# UKHASnet-avr-sensor.net
KiCad netlist of a schematic drawn in EAGLE
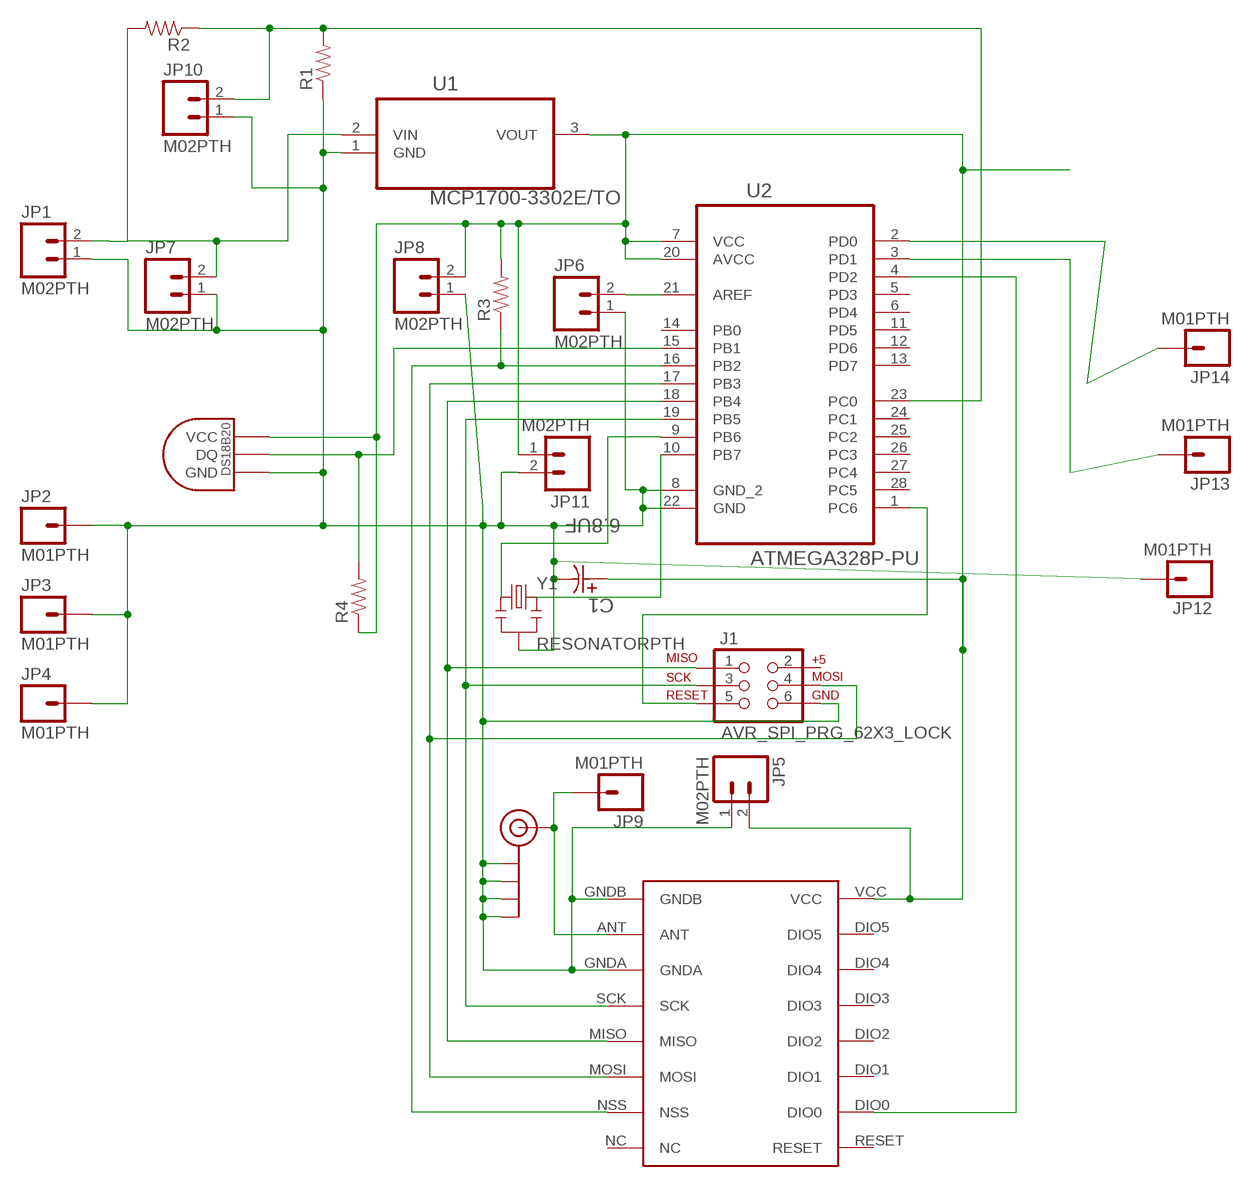
[diagram p0: schematic, sheet 1]

(export (version "E")
  (design (tool "Eeschema 10.0.6"))
  (components
    (comp (ref "C1")
      (value "6.8UF")
      (footprint "eagle-import:CAPPR150-400X1200")
      (fields (field (name "MPN") "EEUFC1J6R8") (field (name "TOLERANCE") "±20 %"))
      (libsource (lib "eagle-import") (part "EEU-P1.5FC1J6R8"))
    )
    (comp (ref "J$1")
      (value "SMA_EDGE")
      (footprint "eagle-import:SMA-EDGE")
      (libsource (lib "eagle-import") (part "SMA_EDGE"))
    )
    (comp (ref "J1")
      (value "AVR_SPI_PRG_62X3_LOCK")
      (footprint "eagle-import:2X3_LOCK")
      (libsource (lib "eagle-import") (part "AVR_SPI_PRG_62X3_LOCK"))
    )
    (comp (ref "JP1")
      (value "M02PTH")
      (footprint "eagle-import:1X02")
      (libsource (lib "eagle-import") (part "M02PTH"))
    )
    (comp (ref "JP2")
      (value "M01PTH")
      (footprint "eagle-import:1X01")
      (libsource (lib "eagle-import") (part "M01PTH"))
    )
    (comp (ref "JP3")
      (value "M01PTH")
      (footprint "eagle-import:1X01")
      (libsource (lib "eagle-import") (part "M01PTH"))
    )
    (comp (ref "JP4")
      (value "M01PTH")
      (footprint "eagle-import:1X01")
      (libsource (lib "eagle-import") (part "M01PTH"))
    )
    (comp (ref "JP5")
      (value "M02PTH")
      (footprint "eagle-import:1X02")
      (libsource (lib "eagle-import") (part "M02PTH"))
    )
    (comp (ref "JP6")
      (value "M02PTH")
      (footprint "eagle-import:1X02")
      (libsource (lib "eagle-import") (part "M02PTH"))
    )
    (comp (ref "JP7")
      (value "M02PTH")
      (footprint "eagle-import:1X02")
      (libsource (lib "eagle-import") (part "M02PTH"))
    )
    (comp (ref "JP8")
      (value "M02PTH")
      (footprint "eagle-import:1X02")
      (libsource (lib "eagle-import") (part "M02PTH"))
    )
    (comp (ref "JP9")
      (value "M01PTH")
      (footprint "eagle-import:1X01")
      (libsource (lib "eagle-import") (part "M01PTH"))
    )
    (comp (ref "JP10")
      (value "M02PTH")
      (footprint "eagle-import:1X02")
      (libsource (lib "eagle-import") (part "M02PTH"))
    )
    (comp (ref "JP11")
      (value "M02PTH")
      (footprint "eagle-import:1X02")
      (libsource (lib "eagle-import") (part "M02PTH"))
    )
    (comp (ref "JP12")
      (value "M01PTH")
      (footprint "eagle-import:1X01")
      (libsource (lib "eagle-import") (part "M01PTH"))
    )
    (comp (ref "JP13")
      (value "M01PTH")
      (footprint "eagle-import:1X01")
      (libsource (lib "eagle-import") (part "M01PTH"))
    )
    (comp (ref "JP14")
      (value "M01PTH")
      (footprint "eagle-import:1X01")
      (libsource (lib "eagle-import") (part "M01PTH"))
    )
    (comp (ref "R1")
      (value "RESISTORPTH-1/4W")
      (footprint "eagle-import:AXIAL-0.4")
      (libsource (lib "eagle-import") (part "RESISTORPTH-1/4W"))
    )
    (comp (ref "R2")
      (value "RESISTORPTH-1/4W")
      (footprint "eagle-import:AXIAL-0.4")
      (libsource (lib "eagle-import") (part "RESISTORPTH-1/4W"))
    )
    (comp (ref "R3")
      (value "RESISTORPTH-1/4W")
      (footprint "eagle-import:AXIAL-0.4")
      (libsource (lib "eagle-import") (part "RESISTORPTH-1/4W"))
    )
    (comp (ref "R4")
      (value "RESISTORPTH-1/4W")
      (footprint "eagle-import:AXIAL-0.4")
      (libsource (lib "eagle-import") (part "RESISTORPTH-1/4W"))
    )
    (comp (ref "U$1")
      (value "RFM69HW")
      (footprint "eagle-import:RFM")
      (libsource (lib "eagle-import") (part "RFM69HW"))
    )
    (comp (ref "U$2")
      (value "DS1820TO92")
      (footprint "eagle-import:DS1820")
      (libsource (lib "eagle-import") (part "DS1820TO92"))
    )
    (comp (ref "U1")
      (value "MCP1700-3302E/TO")
      (footprint "eagle-import:TO127P254X495-3")
      (libsource (lib "eagle-import") (part "MCP1700-3302E/TO"))
    )
    (comp (ref "U2")
      (value "ATMEGA328P-PU")
      (footprint "eagle-import:DIP254P762X457-28")
      (libsource (lib "eagle-import") (part "ATMEGA328P-PU"))
    )
    (comp (ref "Y1")
      (value "RESONATORPTH")
      (footprint "eagle-import:RESONATOR-PTH")
      (libsource (lib "eagle-import") (part "RESONATORPTH"))
    )
  )
  (nets
    (net (code "1") (name "Net-(J$1-SIGNAL)") (class "Default")
      (node (ref "J$1") (pin "SIG") (pinfunction "SIGNAL_SIG") (pintype "bidirectional"))
      (node (ref "JP9") (pin "1") (pinfunction "1_1") (pintype "passive"))
      (node (ref "U$1") (pin "ANT") (pinfunction "ANT_ANT") (pintype "bidirectional"))
    )
    (net (code "2") (name "Net-(R1-1)") (class "Default")
      (node (ref "C1") (pin "2") (pinfunction "2_2") (pintype "passive"))
      (node (ref "J$1") (pin "GND@0") (pinfunction "GND_GND@0") (pintype "bidirectional"))
      (node (ref "J$1") (pin "GND@1") (pinfunction "GND_GND@1") (pintype "bidirectional"))
      (node (ref "J$1") (pin "GND@2") (pinfunction "GND_GND@2") (pintype "bidirectional"))
      (node (ref "J$1") (pin "GND@3") (pinfunction "GND_GND@3") (pintype "bidirectional"))
      (node (ref "J1") (pin "6") (pinfunction "6_6") (pintype "passive"))
      (node (ref "JP1") (pin "1") (pinfunction "1_1") (pintype "passive"))
      (node (ref "JP10") (pin "1") (pinfunction "1_1") (pintype "passive"))
      (node (ref "JP11") (pin "2") (pinfunction "2_2") (pintype "passive"))
      (node (ref "JP12") (pin "1") (pinfunction "1_1") (pintype "passive"))
      (node (ref "JP2") (pin "1") (pinfunction "1_1") (pintype "passive"))
      (node (ref "JP3") (pin "1") (pinfunction "1_1") (pintype "passive"))
      (node (ref "JP4") (pin "1") (pinfunction "1_1") (pintype "passive"))
      (node (ref "JP5") (pin "1") (pinfunction "1_1") (pintype "passive"))
      (node (ref "JP6") (pin "1") (pinfunction "1_1") (pintype "passive"))
      (node (ref "JP7") (pin "1") (pinfunction "1_1") (pintype "passive"))
      (node (ref "JP8") (pin "1") (pinfunction "1_1") (pintype "passive"))
      (node (ref "R1") (pin "P$1") (pinfunction "1_P$1") (pintype "passive"))
      (node (ref "U$1") (pin "GNDA") (pinfunction "GNDA_GNDA") (pintype "bidirectional"))
      (node (ref "U$1") (pin "GNDB") (pinfunction "GNDB_GNDB") (pintype "bidirectional"))
      (node (ref "U$2") (pin "GND") (pinfunction "GND_GND") (pintype "power_in"))
      (node (ref "U1") (pin "1") (pinfunction "GND_1") (pintype "passive"))
      (node (ref "U2") (pin "22") (pinfunction "GND_22") (pintype "passive"))
      (node (ref "U2") (pin "8") (pinfunction "GND_2_8") (pintype "passive"))
      (node (ref "Y1") (pin "2") (pinfunction "2_2") (pintype "passive"))
    )
    (net (code "3") (name "Net-(R1-2)") (class "Default")
      (node (ref "JP10") (pin "2") (pinfunction "2_2") (pintype "passive"))
      (node (ref "R1") (pin "P$2") (pinfunction "2_P$2") (pintype "passive"))
      (node (ref "R2") (pin "P$1") (pinfunction "1_P$1") (pintype "passive"))
      (node (ref "U2") (pin "23") (pinfunction "PC0_23") (pintype "bidirectional"))
    )
    (net (code "4") (name "Net-(R2-2)") (class "Default")
      (node (ref "JP1") (pin "2") (pinfunction "2_2") (pintype "passive"))
      (node (ref "JP7") (pin "2") (pinfunction "2_2") (pintype "passive"))
      (node (ref "R2") (pin "P$2") (pinfunction "2_P$2") (pintype "passive"))
      (node (ref "U1") (pin "2") (pinfunction "VIN_2") (pintype "input"))
    )
    (net (code "5") (name "Net-(R3-1)") (class "Default")
      (node (ref "R3") (pin "P$1") (pinfunction "1_P$1") (pintype "passive"))
      (node (ref "U$1") (pin "NSS") (pinfunction "NSS_NSS") (pintype "bidirectional"))
      (node (ref "U2") (pin "16") (pinfunction "PB2_16") (pintype "bidirectional"))
    )
    (net (code "6") (name "Net-(R3-2)") (class "Default")
      (node (ref "C1") (pin "1") (pinfunction "1_1") (pintype "passive"))
      (node (ref "JP11") (pin "1") (pinfunction "1_1") (pintype "passive"))
      (node (ref "JP5") (pin "2") (pinfunction "2_2") (pintype "passive"))
      (node (ref "JP8") (pin "2") (pinfunction "2_2") (pintype "passive"))
      (node (ref "R3") (pin "P$2") (pinfunction "2_P$2") (pintype "passive"))
      (node (ref "R4") (pin "P$1") (pinfunction "1_P$1") (pintype "passive"))
      (node (ref "U$1") (pin "VCC") (pinfunction "VCC_VCC") (pintype "bidirectional"))
      (node (ref "U$2") (pin "VDD") (pinfunction "VCC_VDD") (pintype "power_in"))
      (node (ref "U1") (pin "3") (pinfunction "VOUT_3") (pintype "output"))
      (node (ref "U2") (pin "20") (pinfunction "AVCC_20") (pintype "power_in"))
      (node (ref "U2") (pin "7") (pinfunction "VCC_7") (pintype "power_in"))
    )
    (net (code "7") (name "Net-(R4-2)") (class "Default")
      (node (ref "R4") (pin "P$2") (pinfunction "2_P$2") (pintype "passive"))
      (node (ref "U$2") (pin "DQ") (pinfunction "DQ_DQ") (pintype "bidirectional"))
      (node (ref "U2") (pin "15") (pinfunction "PB1_15") (pintype "bidirectional"))
    )
    (net (code "8") (name "Net-(U2-AREF)") (class "Default")
      (node (ref "JP6") (pin "2") (pinfunction "2_2") (pintype "passive"))
      (node (ref "U2") (pin "21") (pinfunction "AREF_21") (pintype "input"))
    )
    (net (code "9") (name "Net-(U2-PB3)") (class "Default")
      (node (ref "J1") (pin "4") (pinfunction "4_4") (pintype "passive"))
      (node (ref "U$1") (pin "MOSI") (pinfunction "MOSI_MOSI") (pintype "bidirectional"))
      (node (ref "U2") (pin "17") (pinfunction "PB3_17") (pintype "bidirectional"))
    )
    (net (code "10") (name "Net-(U2-PB4)") (class "Default")
      (node (ref "J1") (pin "1") (pinfunction "1_1") (pintype "passive"))
      (node (ref "U$1") (pin "MISO") (pinfunction "MISO_MISO") (pintype "bidirectional"))
      (node (ref "U2") (pin "18") (pinfunction "PB4_18") (pintype "bidirectional"))
    )
    (net (code "11") (name "Net-(U2-PB5)") (class "Default")
      (node (ref "J1") (pin "3") (pinfunction "3_3") (pintype "passive"))
      (node (ref "U$1") (pin "SCK") (pinfunction "SCK_SCK") (pintype "bidirectional"))
      (node (ref "U2") (pin "19") (pinfunction "PB5_19") (pintype "bidirectional"))
    )
    (net (code "12") (name "Net-(U2-PB6)") (class "Default")
      (node (ref "U2") (pin "9") (pinfunction "PB6_9") (pintype "bidirectional"))
      (node (ref "Y1") (pin "1") (pinfunction "1_1") (pintype "passive"))
    )
    (net (code "13") (name "Net-(U2-PB7)") (class "Default")
      (node (ref "U2") (pin "10") (pinfunction "PB7_10") (pintype "bidirectional"))
      (node (ref "Y1") (pin "3") (pinfunction "3_3") (pintype "passive"))
    )
    (net (code "14") (name "Net-(U2-PC6)") (class "Default")
      (node (ref "J1") (pin "5") (pinfunction "5_5") (pintype "passive"))
      (node (ref "U2") (pin "1") (pinfunction "PC6_1") (pintype "bidirectional"))
    )
    (net (code "15") (name "Net-(U2-PD0)") (class "Default")
      (node (ref "JP14") (pin "1") (pinfunction "1_1") (pintype "passive"))
      (node (ref "U2") (pin "2") (pinfunction "PD0_2") (pintype "bidirectional"))
    )
    (net (code "16") (name "Net-(U2-PD1)") (class "Default")
      (node (ref "JP13") (pin "1") (pinfunction "1_1") (pintype "passive"))
      (node (ref "U2") (pin "3") (pinfunction "PD1_3") (pintype "bidirectional"))
    )
    (net (code "17") (name "Net-(U2-PD2)") (class "Default")
      (node (ref "U$1") (pin "DIO0") (pinfunction "DIO0_DIO0") (pintype "bidirectional"))
      (node (ref "U2") (pin "4") (pinfunction "PD2_4") (pintype "bidirectional"))
    )
    (net (code "18") (name "unconnected-(J1-Pad2)") (class "Default")
      (node (ref "J1") (pin "2") (pinfunction "2_2") (pintype "passive"))
    )
    (net (code "19") (name "unconnected-(U$1-PadDIO1)") (class "Default")
      (node (ref "U$1") (pin "DIO1") (pinfunction "DIO1_DIO1") (pintype "bidirectional"))
    )
    (net (code "20") (name "unconnected-(U$1-PadDIO2)") (class "Default")
      (node (ref "U$1") (pin "DIO2") (pinfunction "DIO2_DIO2") (pintype "bidirectional"))
    )
    (net (code "21") (name "unconnected-(U$1-PadDIO3)") (class "Default")
      (node (ref "U$1") (pin "DIO3") (pinfunction "DIO3_DIO3") (pintype "bidirectional"))
    )
    (net (code "22") (name "unconnected-(U$1-PadDIO4)") (class "Default")
      (node (ref "U$1") (pin "DIO4") (pinfunction "DIO4_DIO4") (pintype "bidirectional"))
    )
    (net (code "23") (name "unconnected-(U$1-PadDIO5)") (class "Default")
      (node (ref "U$1") (pin "DIO5") (pinfunction "DIO5_DIO5") (pintype "bidirectional"))
    )
    (net (code "24") (name "unconnected-(U$1-PadNC)") (class "Default")
      (node (ref "U$1") (pin "NC") (pinfunction "NC_NC") (pintype "bidirectional"))
    )
    (net (code "25") (name "unconnected-(U$1-PadRESET)") (class "Default")
      (node (ref "U$1") (pin "RESET") (pinfunction "RESET_RESET") (pintype "bidirectional"))
    )
    (net (code "26") (name "unconnected-(U2-PB0-Pad14)") (class "Default")
      (node (ref "U2") (pin "14") (pinfunction "PB0_14") (pintype "bidirectional"))
    )
    (net (code "27") (name "unconnected-(U2-PC1-Pad24)") (class "Default")
      (node (ref "U2") (pin "24") (pinfunction "PC1_24") (pintype "bidirectional"))
    )
    (net (code "28") (name "unconnected-(U2-PC2-Pad25)") (class "Default")
      (node (ref "U2") (pin "25") (pinfunction "PC2_25") (pintype "bidirectional"))
    )
    (net (code "29") (name "unconnected-(U2-PC3-Pad26)") (class "Default")
      (node (ref "U2") (pin "26") (pinfunction "PC3_26") (pintype "bidirectional"))
    )
    (net (code "30") (name "unconnected-(U2-PC4-Pad27)") (class "Default")
      (node (ref "U2") (pin "27") (pinfunction "PC4_27") (pintype "bidirectional"))
    )
    (net (code "31") (name "unconnected-(U2-PC5-Pad28)") (class "Default")
      (node (ref "U2") (pin "28") (pinfunction "PC5_28") (pintype "bidirectional"))
    )
    (net (code "32") (name "unconnected-(U2-PD3-Pad5)") (class "Default")
      (node (ref "U2") (pin "5") (pinfunction "PD3_5") (pintype "bidirectional"))
    )
    (net (code "33") (name "unconnected-(U2-PD4-Pad6)") (class "Default")
      (node (ref "U2") (pin "6") (pinfunction "PD4_6") (pintype "bidirectional"))
    )
    (net (code "34") (name "unconnected-(U2-PD5-Pad11)") (class "Default")
      (node (ref "U2") (pin "11") (pinfunction "PD5_11") (pintype "bidirectional"))
    )
    (net (code "35") (name "unconnected-(U2-PD6-Pad12)") (class "Default")
      (node (ref "U2") (pin "12") (pinfunction "PD6_12") (pintype "bidirectional"))
    )
    (net (code "36") (name "unconnected-(U2-PD7-Pad13)") (class "Default")
      (node (ref "U2") (pin "13") (pinfunction "PD7_13") (pintype "bidirectional"))
    )
  )
)
